# diff2singleEnded.net
KiCad netlist of a schematic drawn in Altium Designer
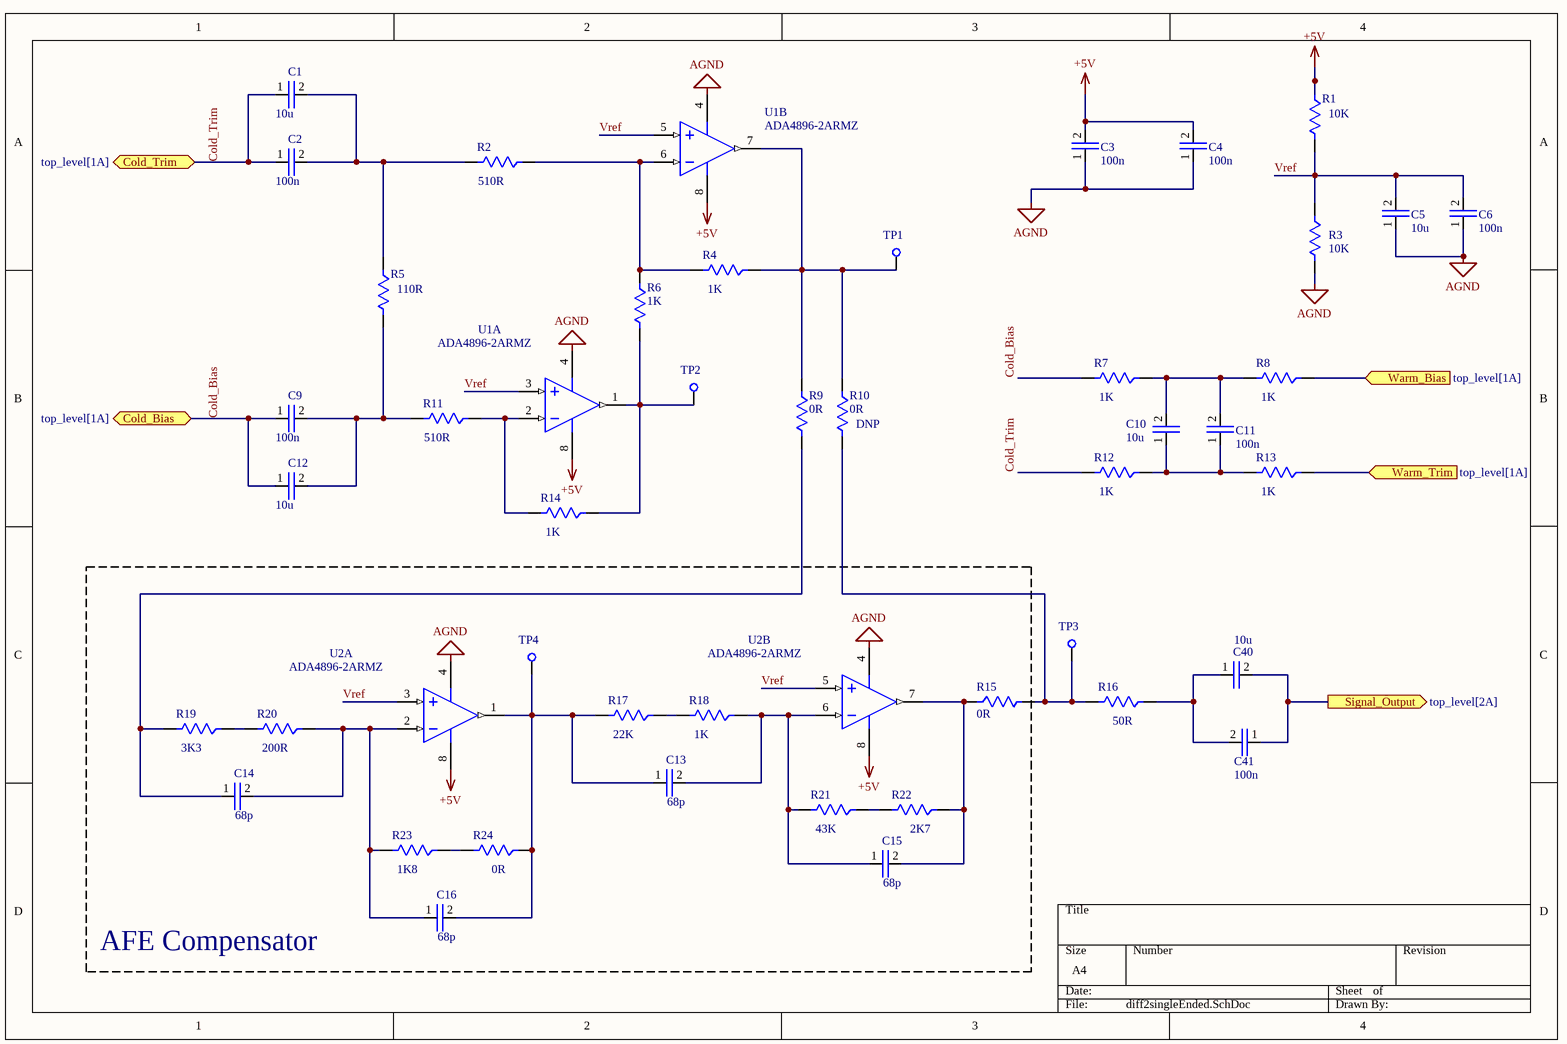
[diagram p0: diff2singleEnded.SchDoc]

(export (version "E")
  (design (tool "Eeschema 10.0.6"))
  (components
    (comp (ref "C1")
      (value "10u")
      (footprint "CAPC3216X190N")
      (description "10 µF ±10% 100V Ceramic Capacitor X6S 1206 (3216 Metric)")
      (fields (field (name "MP") "C3216X6S2A106K160AC"))
      (libsource (lib "ChipCapacitor_1206") (part "Capacitor"))
    )
    (comp (ref "C2")
      (value "100n")
      (footprint "CAPC1608X09N")
      (description "0.1 µF ±10% 100V Ceramic Capacitor X7R 0603 (1608 Metric)")
      (fields (field (name "MP") "CC0603KRX7R0BB104"))
      (libsource (lib "Capacitor_0603") (part "Capacitor"))
    )
    (comp (ref "C3")
      (value "100n")
      (footprint "CAPC1608X09N")
      (description "0.1 µF ±10% 100V Ceramic Capacitor X7R 0603 (1608 Metric)")
      (fields (field (name "MP") "CC0603KRX7R0BB104"))
      (libsource (lib "Capacitor_0603") (part "Capacitor"))
    )
    (comp (ref "C4")
      (value "100n")
      (footprint "CAPC1608X09N")
      (description "0.1 µF ±10% 100V Ceramic Capacitor X7R 0603 (1608 Metric)")
      (fields (field (name "MP") "CC0603KRX7R0BB104"))
      (libsource (lib "Capacitor_0603") (part "Capacitor"))
    )
    (comp (ref "C5")
      (value "10u")
      (footprint "CAPC3216X190N")
      (description "10 µF ±10% 10V Ceramic Capacitor X5R 1206 (3216 Metric)")
      (fields (field (name "MP") "CL31A106KPHNNNE"))
      (libsource (lib "ChipCapacitor_1206") (part "Capacitor"))
    )
    (comp (ref "C6")
      (value "100n")
      (footprint "CAPC1608X09N")
      (description "0.1 µF ±10% 100V Ceramic Capacitor X7R 0603 (1608 Metric)")
      (fields (field (name "MP") "CC0603KRX7R0BB104"))
      (libsource (lib "Capacitor_0603") (part "Capacitor"))
    )
    (comp (ref "C9")
      (value "100n")
      (footprint "CAPC1608X09N")
      (description "0.1 µF ±10% 100V Ceramic Capacitor X7R 0603 (1608 Metric)")
      (fields (field (name "MP") "CC0603KRX7R0BB104"))
      (libsource (lib "Capacitor_0603") (part "Capacitor"))
    )
    (comp (ref "C10")
      (value "10u")
      (footprint "CAPC3216X190N")
      (description "10 µF ±10% 100V Ceramic Capacitor X6S 1206 (3216 Metric)")
      (fields (field (name "MP") "C3216X6S2A106K160AC"))
      (libsource (lib "ChipCapacitor_1206") (part "Capacitor"))
    )
    (comp (ref "C11")
      (value "100n")
      (footprint "CAPC1608X09N")
      (description "0.1 µF ±10% 100V Ceramic Capacitor X7R 0603 (1608 Metric)")
      (fields (field (name "MP") "CC0603KRX7R0BB104"))
      (libsource (lib "Capacitor_0603") (part "Capacitor"))
    )
    (comp (ref "C12")
      (value "10u")
      (footprint "CAPC3216X190N")
      (description "10 µF ±10% 100V Ceramic Capacitor X6S 1206 (3216 Metric)")
      (fields (field (name "MP") "C3216X6S2A106K160AC"))
      (libsource (lib "ChipCapacitor_1206") (part "Capacitor"))
    )
    (comp (ref "C13")
      (value "68p")
      (footprint "CAPC1608X09N")
      (description "68 pF ±1% 100V Ceramic Capacitor C0G, NP0 0603 (1608 Metric)")
      (fields (field (name "MP") "GCM1885C2A680FA16D"))
      (libsource (lib "Capacitor_0603") (part "Capacitor"))
    )
    (comp (ref "C14")
      (value "68p")
      (footprint "CAPC1608X09N")
      (description "68 pF ±1% 100V Ceramic Capacitor C0G, NP0 0603 (1608 Metric)")
      (fields (field (name "MP") "GCM1885C2A680FA16D"))
      (libsource (lib "Capacitor_0603") (part "Capacitor"))
    )
    (comp (ref "C15")
      (value "68p")
      (footprint "CAPC1608X09N")
      (description "68 pF ±1% 100V Ceramic Capacitor C0G, NP0 0603 (1608 Metric)")
      (fields (field (name "MP") "GCM1885C2A680FA16D"))
      (libsource (lib "Capacitor_0603") (part "Capacitor"))
    )
    (comp (ref "C16")
      (value "68p")
      (footprint "CAPC1608X09N")
      (description "68 pF ±1% 100V Ceramic Capacitor C0G, NP0 0603 (1608 Metric)")
      (fields (field (name "MP") "GCM1885C2A680FA16D"))
      (libsource (lib "Capacitor_0603") (part "Capacitor"))
    )
    (comp (ref "C40")
      (value "10u")
      (footprint "CAPC1608X09N")
      (description "10 µF ±10% 10V Ceramic Capacitor X5R 0603 (1608 Metric)")
      (fields (field (name "MP") "CL10A106KP8NNNC"))
      (libsource (lib "Capacitor_0603") (part "Capacitor"))
    )
    (comp (ref "C41")
      (value "100n")
      (footprint "CAPC1608X09N")
      (description "0.1 µF ±10% 100V Ceramic Capacitor X7R 0603 (1608 Metric)")
      (fields (field (name "MP") "CC0603KRX7R0BB104"))
      (libsource (lib "Capacitor_0603") (part "Capacitor"))
    )
    (comp (ref "R1")
      (value "10K")
      (footprint "RESC1608X55N")
      (description "10 kOhms ±1% 0.1W, 1/10W Chip Resistor 0603 (1608 Metric) Moisture Resistant Thick Film")
      (fields (field (name "MP") "RC0603FR-0710KL"))
      (libsource (lib "ChipResistor_0603") (part "Resistor"))
    )
    (comp (ref "R2")
      (value "510R")
      (footprint "RESC1608X55N")
      (description "510 Ohms ±0.1% 0.1W, 1/10W Chip Resistor 0603 (1608 Metric) Thin Film")
      (fields (field (name "MP") "RT0603BRD07510RL"))
      (libsource (lib "ChipResistor_0603") (part "Resistor"))
    )
    (comp (ref "R3")
      (value "10K")
      (footprint "RESC1608X55N")
      (description "10 kOhms ±1% 0.1W, 1/10W Chip Resistor 0603 (1608 Metric) Moisture Resistant Thick Film")
      (fields (field (name "MP") "RC0603FR-0710KL"))
      (libsource (lib "ChipResistor_0603") (part "Resistor"))
    )
    (comp (ref "R4")
      (value "1K")
      (footprint "RESC1608X55N")
      (description "1 kOhms ±0.1% 0.1W, 1/10W Chip Resistor 0603 (1608 Metric) Thin Film")
      (fields (field (name "MP") "RT0603BRD071KL"))
      (libsource (lib "ChipResistor_0603") (part "Resistor"))
    )
    (comp (ref "R5")
      (value "110R")
      (footprint "RESC1608X55N")
      (description "110 Ohms ±0.1% 0.1W, 1/10W Chip Resistor 0603 (1608 Metric) Thin Film")
      (fields (field (name "MP") "RT0603BRD07110RL"))
      (libsource (lib "ChipResistor_0603") (part "Resistor"))
    )
    (comp (ref "R6")
      (value "1K")
      (footprint "RESC1608X55N")
      (description "1 kOhms ±0.1% 0.1W, 1/10W Chip Resistor 0603 (1608 Metric) Thin Film")
      (fields (field (name "MP") "RT0603BRD071KL"))
      (libsource (lib "ChipResistor_0603") (part "Resistor"))
    )
    (comp (ref "R7")
      (value "1K")
      (footprint "RESC1608X55N")
      (description "1 kOhms ±0.1% 0.1W, 1/10W Chip Resistor 0603 (1608 Metric) Thin Film")
      (fields (field (name "MP") "RT0603BRD071KL"))
      (libsource (lib "ChipResistor_0603") (part "Resistor"))
    )
    (comp (ref "R8")
      (value "1K")
      (footprint "RESC1608X55N")
      (description "1 kOhms ±0.1% 0.1W, 1/10W Chip Resistor 0603 (1608 Metric) Thin Film")
      (fields (field (name "MP") "RT0603BRD071KL"))
      (libsource (lib "ChipResistor_0603") (part "Resistor"))
    )
    (comp (ref "R9")
      (value "0R")
      (footprint "RESC1608X55N")
      (description "0 Ohms Jumper Chip Resistor 0603 (1608 Metric) Automotive AEC-Q200 Thick Film")
      (fields (field (name "MP") "RMCF0603ZT0R00"))
      (libsource (lib "ChipResistor_0603") (part "Resistor"))
    )
    (comp (ref "R10")
      (value "DNP")
      (footprint "RESC1608X55N")
      (description "0 Ohms Jumper Chip Resistor 0603 (1608 Metric) Automotive AEC-Q200 Thick Film")
      (fields (field (name "ALTIUM_VALUE") "0R") (field (name "MP") "RMCF0603ZT0R00"))
      (libsource (lib "ChipResistor_0603") (part "Resistor"))
    )
    (comp (ref "R11")
      (value "510R")
      (footprint "RESC1608X55N")
      (description "510 Ohms ±0.1% 0.1W, 1/10W Chip Resistor 0603 (1608 Metric) Thin Film")
      (fields (field (name "MP") "RT0603BRD07510RL"))
      (libsource (lib "ChipResistor_0603") (part "Resistor"))
    )
    (comp (ref "R12")
      (value "1K")
      (footprint "RESC1608X55N")
      (description "1 kOhms ±0.1% 0.1W, 1/10W Chip Resistor 0603 (1608 Metric) Thin Film")
      (fields (field (name "MP") "RT0603BRD071KL"))
      (libsource (lib "ChipResistor_0603") (part "Resistor"))
    )
    (comp (ref "R13")
      (value "1K")
      (footprint "RESC1608X55N")
      (description "1 kOhms ±0.1% 0.1W, 1/10W Chip Resistor 0603 (1608 Metric) Thin Film")
      (fields (field (name "MP") "RT0603BRD071KL"))
      (libsource (lib "ChipResistor_0603") (part "Resistor"))
    )
    (comp (ref "R14")
      (value "1K")
      (footprint "RESC1608X55N")
      (description "1 kOhms ±0.1% 0.1W, 1/10W Chip Resistor 0603 (1608 Metric) Thin Film")
      (fields (field (name "MP") "RT0603BRD071KL"))
      (libsource (lib "ChipResistor_0603") (part "Resistor"))
    )
    (comp (ref "R15")
      (value "0R")
      (footprint "RESC1608X55N")
      (description "0 Ohms Jumper Chip Resistor 0603 (1608 Metric) Automotive AEC-Q200 Thick Film")
      (fields (field (name "MP") "RMCF0603ZT0R00"))
      (libsource (lib "ChipResistor_0603") (part "Resistor"))
    )
    (comp (ref "R16")
      (value "50R")
      (footprint "RESC1608X55N")
      (description "50 Ohms ±0.1% 0.1W, 1/10W Chip Resistor 0603 (1608 Metric) Thin Film")
      (fields (field (name "MP") "RT0603BRE0750RL"))
      (libsource (lib "ChipResistor_0603") (part "Resistor"))
    )
    (comp (ref "R17")
      (value "22K")
      (footprint "RESC1608X55N")
      (description "22 kOhms ±0.1% 0.1W, 1/10W Chip Resistor 0603 (1608 Metric) Thin Film")
      (fields (field (name "MP") "RT0603BRE0722KL"))
      (libsource (lib "ChipResistor_0603") (part "Resistor"))
    )
    (comp (ref "R18")
      (value "1K")
      (footprint "RESC1608X55N")
      (description "1 kOhms ±0.1% 0.1W, 1/10W Chip Resistor 0603 (1608 Metric) Thin Film")
      (fields (field (name "MP") "RT0603BRD071KL"))
      (libsource (lib "ChipResistor_0603") (part "Resistor"))
    )
    (comp (ref "R19")
      (value "3K3")
      (footprint "RESC1608X55N")
      (description "3.3 kOhms ±0.1% 0.1W, 1/10W Chip Resistor 0603 (1608 Metric) Thin Film")
      (fields (field (name "MP") "RT0603BRD073K3L"))
      (libsource (lib "ChipResistor_0603") (part "Resistor"))
    )
    (comp (ref "R20")
      (value "200R")
      (footprint "RESC1608X55N")
      (description "200 Ohms ±0.1% 0.1W, 1/10W Chip Resistor 0603 (1608 Metric) Thin Film")
      (fields (field (name "MP") "RT0603BRD07200RL"))
      (libsource (lib "ChipResistor_0603") (part "Resistor"))
    )
    (comp (ref "R21")
      (value "43K")
      (footprint "RESC1608X55N")
      (description "43 kOhms ±0.1% 0.1W, 1/10W Chip Resistor 0603 (1608 Metric) Thin Film")
      (fields (field (name "MP") "RT0603BRD0743KL"))
      (libsource (lib "ChipResistor_0603") (part "Resistor"))
    )
    (comp (ref "R22")
      (value "2K7")
      (footprint "RESC1608X55N")
      (description "2.7 kOhms ±0.1% 0.1W, 1/10W Chip Resistor 0603 (1608 Metric) Thin Film")
      (fields (field (name "MP") "RT0603BRD072K7L"))
      (libsource (lib "ChipResistor_0603") (part "Resistor"))
    )
    (comp (ref "R23")
      (value "1K8")
      (footprint "RESC1608X55N")
      (description "1.8 kOhms ±0.1% 0.1W, 1/10W Chip Resistor 0603 (1608 Metric) Thin Film")
      (fields (field (name "MP") "RT0603BRD071K8L"))
      (libsource (lib "ChipResistor_0603") (part "Resistor"))
    )
    (comp (ref "R24")
      (value "0R")
      (footprint "RESC1608X55N")
      (description "0 Ohms Jumper Chip Resistor 0603 (1608 Metric) Automotive AEC-Q200 Thick Film")
      (fields (field (name "MP") "RMCF0603ZT0R00"))
      (libsource (lib "ChipResistor_0603") (part "Resistor"))
    )
    (comp (ref "TP1")
      (value "testPoint")
      (footprint "testPoint_pad")
      (libsource (lib "testPoint") (part "testPoint"))
    )
    (comp (ref "TP2")
      (value "testPoint")
      (footprint "testPoint_pad")
      (libsource (lib "testPoint") (part "testPoint"))
    )
    (comp (ref "TP3")
      (value "testPoint")
      (footprint "testPoint_pad")
      (libsource (lib "testPoint") (part "testPoint"))
    )
    (comp (ref "TP4")
      (value "testPoint")
      (footprint "testPoint_pad")
      (libsource (lib "testPoint") (part "testPoint"))
    )
    (comp (ref "U1")
      (value "ADA4896-2ARMZ")
      (footprint "ADI-RM-8_N")
      (fields (field (name "GENERIC PART NUMBER") "ADA4896-2") (field (name "MANUFACTURER") "Analog Devices"))
      (libsource (lib "ADA4896-2ARMZ") (part "CMP-0384-01715-1"))
    )
    (comp (ref "U2")
      (value "ADA4896-2ARMZ")
      (footprint "ADI-RM-8_N")
      (fields (field (name "GENERIC PART NUMBER") "ADA4896-2") (field (name "MANUFACTURER") "Analog Devices"))
      (libsource (lib "ADA4896-2ARMZ") (part "CMP-0384-01715-1"))
    )
  )
  (nets
    (net (code "1") (name "+5V") (class "Default")
      (node (ref "C3") (pin "2") (pinfunction "2_2") (pintype "passive"))
      (node (ref "C4") (pin "2") (pinfunction "2_2") (pintype "passive"))
      (node (ref "R1") (pin "2") (pinfunction "2_2") (pintype "passive"))
      (node (ref "U1") (pin "8") (pinfunction "+VS_8") (pintype "power_in"))
      (node (ref "U2") (pin "8") (pinfunction "+VS_8") (pintype "power_in"))
    )
    (net (code "2") (name "/Cold_Bias") (class "Default")
      (node (ref "C12") (pin "1") (pinfunction "2_1") (pintype "passive"))
      (node (ref "C9") (pin "1") (pinfunction "2_1") (pintype "passive"))
      (node (ref "R7") (pin "1") (pinfunction "1_1") (pintype "passive"))
    )
    (net (code "3") (name "/Cold_Trim") (class "Default")
      (node (ref "C1") (pin "1") (pinfunction "2_1") (pintype "passive"))
      (node (ref "C2") (pin "1") (pinfunction "2_1") (pintype "passive"))
      (node (ref "R12") (pin "1") (pinfunction "1_1") (pintype "passive"))
    )
    (net (code "4") (name "/Signal_Output") (class "Default")
      (node (ref "C40") (pin "2") (pinfunction "2_2") (pintype "passive"))
      (node (ref "C41") (pin "1") (pinfunction "2_1") (pintype "passive"))
    )
    (net (code "5") (name "/Vref") (class "Default")
      (node (ref "C5") (pin "2") (pinfunction "2_2") (pintype "passive"))
      (node (ref "C6") (pin "2") (pinfunction "2_2") (pintype "passive"))
      (node (ref "R1") (pin "1") (pinfunction "1_1") (pintype "passive"))
      (node (ref "R3") (pin "2") (pinfunction "2_2") (pintype "passive"))
      (node (ref "U1") (pin "3") (pinfunction "+IN_1_3") (pintype "input"))
      (node (ref "U1") (pin "5") (pinfunction "+IN_2_5") (pintype "input"))
      (node (ref "U2") (pin "3") (pinfunction "+IN_1_3") (pintype "input"))
      (node (ref "U2") (pin "5") (pinfunction "+IN_2_5") (pintype "input"))
    )
    (net (code "6") (name "/Warm_Bias") (class "Default")
      (node (ref "R8") (pin "2") (pinfunction "2_2") (pintype "passive"))
    )
    (net (code "7") (name "/Warm_Trim") (class "Default")
      (node (ref "R13") (pin "2") (pinfunction "2_2") (pintype "passive"))
    )
    (net (code "8") (name "AGND") (class "Default")
      (node (ref "C3") (pin "1") (pinfunction "2_1") (pintype "passive"))
      (node (ref "C4") (pin "1") (pinfunction "2_1") (pintype "passive"))
      (node (ref "C5") (pin "1") (pinfunction "2_1") (pintype "passive"))
      (node (ref "C6") (pin "1") (pinfunction "2_1") (pintype "passive"))
      (node (ref "R3") (pin "1") (pinfunction "1_1") (pintype "passive"))
      (node (ref "U1") (pin "4") (pinfunction "-VS_4") (pintype "power_in"))
      (node (ref "U2") (pin "4") (pinfunction "-VS_4") (pintype "power_in"))
    )
    (net (code "9") (name "Net-(C1-Pad2)") (class "Default")
      (node (ref "C1") (pin "2") (pinfunction "2_2") (pintype "passive"))
      (node (ref "C2") (pin "2") (pinfunction "2_2") (pintype "passive"))
      (node (ref "R2") (pin "1") (pinfunction "1_1") (pintype "passive"))
      (node (ref "R5") (pin "2") (pinfunction "2_2") (pintype "passive"))
    )
    (net (code "10") (name "Net-(C10-2-Pad1)") (class "Default")
      (node (ref "C10") (pin "1") (pinfunction "2_1") (pintype "passive"))
      (node (ref "C11") (pin "1") (pinfunction "2_1") (pintype "passive"))
      (node (ref "R12") (pin "2") (pinfunction "2_2") (pintype "passive"))
      (node (ref "R13") (pin "1") (pinfunction "1_1") (pintype "passive"))
    )
    (net (code "11") (name "Net-(C10-Pad2)") (class "Default")
      (node (ref "C10") (pin "2") (pinfunction "2_2") (pintype "passive"))
      (node (ref "C11") (pin "2") (pinfunction "2_2") (pintype "passive"))
      (node (ref "R7") (pin "2") (pinfunction "2_2") (pintype "passive"))
      (node (ref "R8") (pin "1") (pinfunction "1_1") (pintype "passive"))
    )
    (net (code "12") (name "Net-(C12-Pad2)") (class "Default")
      (node (ref "C12") (pin "2") (pinfunction "2_2") (pintype "passive"))
      (node (ref "C9") (pin "2") (pinfunction "2_2") (pintype "passive"))
      (node (ref "R11") (pin "1") (pinfunction "1_1") (pintype "passive"))
      (node (ref "R5") (pin "1") (pinfunction "1_1") (pintype "passive"))
    )
    (net (code "13") (name "Net-(C14-2-Pad1)") (class "Default")
      (node (ref "C14") (pin "1") (pinfunction "2_1") (pintype "passive"))
      (node (ref "R19") (pin "1") (pinfunction "1_1") (pintype "passive"))
      (node (ref "R9") (pin "1") (pinfunction "1_1") (pintype "passive"))
    )
    (net (code "14") (name "Net-(C40-2-Pad1)") (class "Default")
      (node (ref "C40") (pin "1") (pinfunction "2_1") (pintype "passive"))
      (node (ref "C41") (pin "2") (pinfunction "2_2") (pintype "passive"))
      (node (ref "R16") (pin "2") (pinfunction "2_2") (pintype "passive"))
    )
    (net (code "15") (name "Net-(R10-Pad1)") (class "Default")
      (node (ref "R10") (pin "1") (pinfunction "1_1") (pintype "passive"))
      (node (ref "R15") (pin "1") (pinfunction "1_1") (pintype "passive"))
      (node (ref "R16") (pin "1") (pinfunction "1_1") (pintype "passive"))
      (node (ref "TP3") (pin "0") (pintype "passive"))
    )
    (net (code "16") (name "Net-(R17-Pad2)") (class "Default")
      (node (ref "R17") (pin "2") (pinfunction "2_2") (pintype "passive"))
      (node (ref "R18") (pin "1") (pinfunction "1_1") (pintype "passive"))
    )
    (net (code "17") (name "Net-(R19-Pad2)") (class "Default")
      (node (ref "R19") (pin "2") (pinfunction "2_2") (pintype "passive"))
      (node (ref "R20") (pin "1") (pinfunction "1_1") (pintype "passive"))
    )
    (net (code "18") (name "Net-(R21-Pad2)") (class "Default")
      (node (ref "R21") (pin "2") (pinfunction "2_2") (pintype "passive"))
      (node (ref "R22") (pin "1") (pinfunction "1_1") (pintype "passive"))
    )
    (net (code "19") (name "Net-(R23-Pad2)") (class "Default")
      (node (ref "R23") (pin "2") (pinfunction "2_2") (pintype "passive"))
      (node (ref "R24") (pin "1") (pinfunction "1_1") (pintype "passive"))
    )
    (net (code "20") (name "Net-(U1A--IN_1)") (class "Default")
      (node (ref "R11") (pin "2") (pinfunction "2_2") (pintype "passive"))
      (node (ref "R14") (pin "1") (pinfunction "1_1") (pintype "passive"))
      (node (ref "U1") (pin "2") (pinfunction "-IN_1_2") (pintype "input"))
    )
    (net (code "21") (name "Net-(U1A-OUT_1)") (class "Default")
      (node (ref "R14") (pin "2") (pinfunction "2_2") (pintype "passive"))
      (node (ref "R6") (pin "1") (pinfunction "1_1") (pintype "passive"))
      (node (ref "TP2") (pin "0") (pintype "passive"))
      (node (ref "U1") (pin "1") (pinfunction "OUT_1_1") (pintype "output"))
    )
    (net (code "22") (name "Net-(U1B--IN_2)") (class "Default")
      (node (ref "R2") (pin "2") (pinfunction "2_2") (pintype "passive"))
      (node (ref "R4") (pin "1") (pinfunction "1_1") (pintype "passive"))
      (node (ref "R6") (pin "2") (pinfunction "2_2") (pintype "passive"))
      (node (ref "U1") (pin "6") (pinfunction "-IN_2_6") (pintype "input"))
    )
    (net (code "23") (name "Net-(U1B-OUT_2)") (class "Default")
      (node (ref "R10") (pin "2") (pinfunction "2_2") (pintype "passive"))
      (node (ref "R4") (pin "2") (pinfunction "2_2") (pintype "passive"))
      (node (ref "R9") (pin "2") (pinfunction "2_2") (pintype "passive"))
      (node (ref "TP1") (pin "0") (pintype "passive"))
      (node (ref "U1") (pin "7") (pinfunction "OUT_2_7") (pintype "output"))
    )
    (net (code "24") (name "Net-(U2A--IN_1)") (class "Default")
      (node (ref "C14") (pin "2") (pinfunction "2_2") (pintype "passive"))
      (node (ref "C16") (pin "1") (pinfunction "2_1") (pintype "passive"))
      (node (ref "R20") (pin "2") (pinfunction "2_2") (pintype "passive"))
      (node (ref "R23") (pin "1") (pinfunction "1_1") (pintype "passive"))
      (node (ref "U2") (pin "2") (pinfunction "-IN_1_2") (pintype "input"))
    )
    (net (code "25") (name "Net-(U2A-OUT_1)") (class "Default")
      (node (ref "C13") (pin "1") (pinfunction "2_1") (pintype "passive"))
      (node (ref "C16") (pin "2") (pinfunction "2_2") (pintype "passive"))
      (node (ref "R17") (pin "1") (pinfunction "1_1") (pintype "passive"))
      (node (ref "R24") (pin "2") (pinfunction "2_2") (pintype "passive"))
      (node (ref "TP4") (pin "0") (pintype "passive"))
      (node (ref "U2") (pin "1") (pinfunction "OUT_1_1") (pintype "output"))
    )
    (net (code "26") (name "Net-(U2B--IN_2)") (class "Default")
      (node (ref "C13") (pin "2") (pinfunction "2_2") (pintype "passive"))
      (node (ref "C15") (pin "1") (pinfunction "2_1") (pintype "passive"))
      (node (ref "R18") (pin "2") (pinfunction "2_2") (pintype "passive"))
      (node (ref "R21") (pin "1") (pinfunction "1_1") (pintype "passive"))
      (node (ref "U2") (pin "6") (pinfunction "-IN_2_6") (pintype "input"))
    )
    (net (code "27") (name "Net-(U2B-OUT_2)") (class "Default")
      (node (ref "C15") (pin "2") (pinfunction "2_2") (pintype "passive"))
      (node (ref "R15") (pin "2") (pinfunction "2_2") (pintype "passive"))
      (node (ref "R22") (pin "2") (pinfunction "2_2") (pintype "passive"))
      (node (ref "U2") (pin "7") (pinfunction "OUT_2_7") (pintype "output"))
    )
  )
)
